# HandTracker.net
KiCad netlist of a schematic drawn in EAGLE
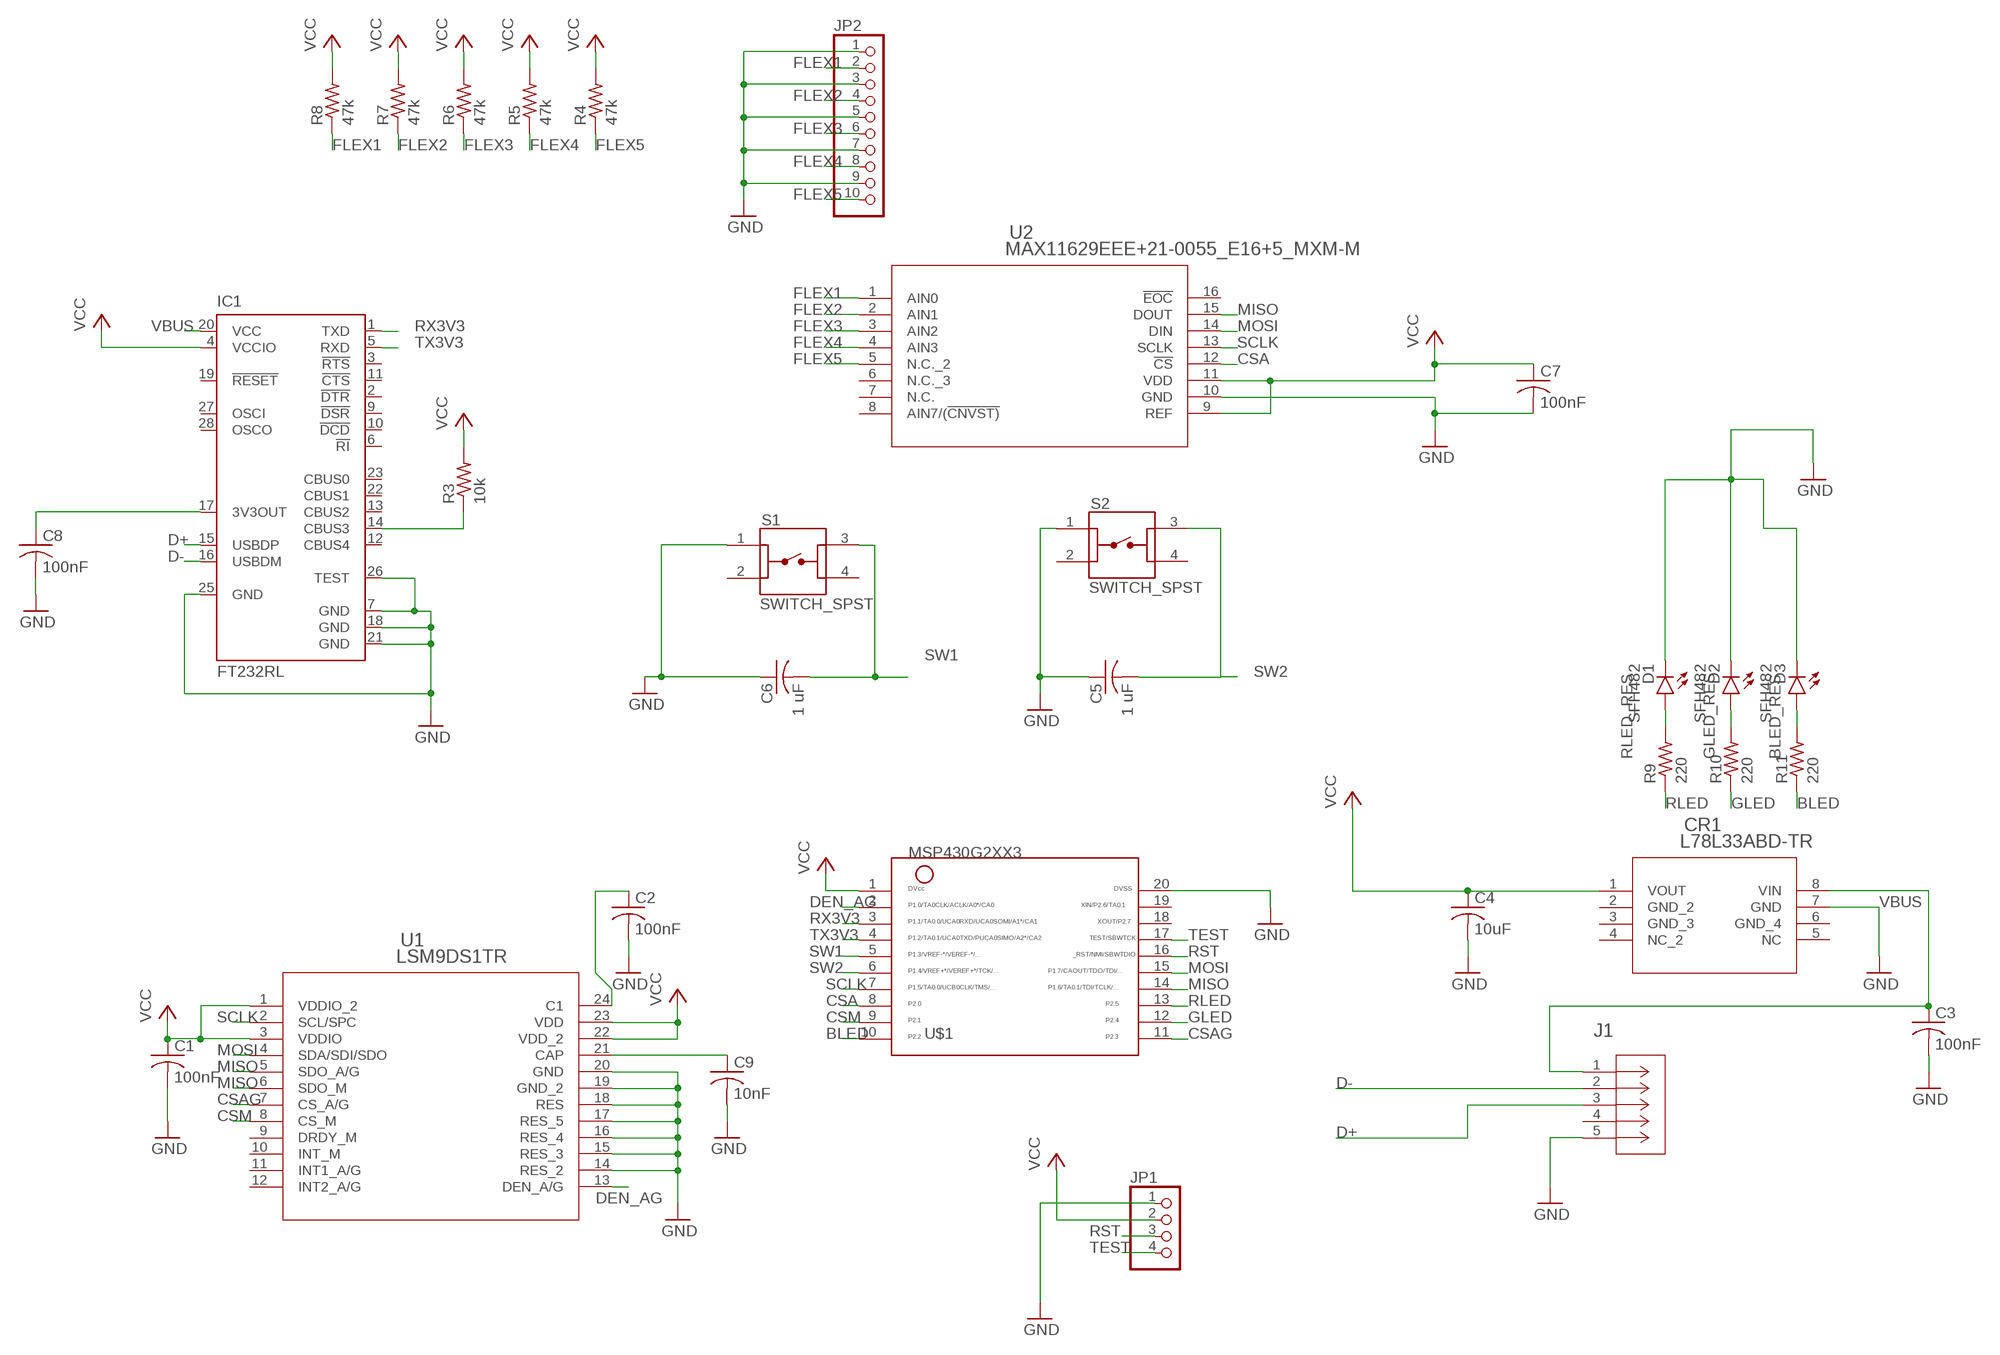
[diagram p0: schematic, sheet 1]

(export (version "E")
  (design (tool "Eeschema 10.0.6"))
  (components
    (comp (ref "C1")
      (value "100nF")
      (footprint "eagle-import:C1206")
      (libsource (lib "eagle-import") (part "C-USC1206"))
    )
    (comp (ref "C2")
      (value "100nF")
      (footprint "eagle-import:C1206")
      (libsource (lib "eagle-import") (part "C-USC1206"))
    )
    (comp (ref "C3")
      (value "100nF")
      (footprint "eagle-import:C1206")
      (libsource (lib "eagle-import") (part "C-USC1206"))
    )
    (comp (ref "C4")
      (value "10uF")
      (footprint "eagle-import:C1206")
      (libsource (lib "eagle-import") (part "C-USC1206"))
    )
    (comp (ref "C5")
      (value "1 uF")
      (footprint "eagle-import:C1206")
      (libsource (lib "eagle-import") (part "C-USC1206"))
    )
    (comp (ref "C6")
      (value "1 uF")
      (footprint "eagle-import:C1206")
      (libsource (lib "eagle-import") (part "C-USC1206"))
    )
    (comp (ref "C7")
      (value "100nF")
      (footprint "eagle-import:C1206")
      (libsource (lib "eagle-import") (part "C-USC1206"))
    )
    (comp (ref "C8")
      (value "100nF")
      (footprint "eagle-import:C1206")
      (libsource (lib "eagle-import") (part "C-USC1206"))
    )
    (comp (ref "C9")
      (value "10nF")
      (footprint "eagle-import:C1206")
      (libsource (lib "eagle-import") (part "C-USC1206"))
    )
    (comp (ref "CR1")
      (value "L78L33ABD-TR")
      (footprint "eagle-import:SO-8_STM")
      (fields (field (name "COPYRIGHT") "Copyright (C) 2022 Ultra Librarian. All rights reserved."))
      (libsource (lib "eagle-import") (part "L78L33ABD-TR"))
    )
    (comp (ref "D1")
      (value "SFH482")
      (footprint "eagle-import:SFH482")
      (libsource (lib "eagle-import") (part "SFH482"))
    )
    (comp (ref "D2")
      (value "SFH482")
      (footprint "eagle-import:SFH482")
      (libsource (lib "eagle-import") (part "SFH482"))
    )
    (comp (ref "D3")
      (value "SFH482")
      (footprint "eagle-import:SFH482")
      (libsource (lib "eagle-import") (part "SFH482"))
    )
    (comp (ref "IC1")
      (value "FT232RL")
      (footprint "eagle-import:SSOP28")
      (libsource (lib "eagle-import") (part "FT232RL"))
    )
    (comp (ref "J1")
      (value "ZX62-AB-5PA(31)")
      (footprint "eagle-import:CONN5_ZX62-AB-5PA_HIR")
      (fields (field (name "COPYRIGHT") "Copyright (C) 2022 Ultra Librarian. All rights reserved."))
      (libsource (lib "eagle-import") (part "ZX62-AB-5PA(31)"))
    )
    (comp (ref "JP1")
      (value "PINHD-1X4/90")
      (footprint "eagle-import:1X04_90")
      (libsource (lib "eagle-import") (part "PINHD-1X4/90"))
    )
    (comp (ref "JP2")
      (value "PINHD-1X10")
      (footprint "eagle-import:1X10")
      (libsource (lib "eagle-import") (part "PINHD-1X10"))
    )
    (comp (ref "R3")
      (value "10k")
      (footprint "eagle-import:R1206")
      (libsource (lib "eagle-import") (part "R-US_R1206"))
    )
    (comp (ref "R4")
      (value "47k")
      (footprint "eagle-import:R1206")
      (libsource (lib "eagle-import") (part "R-US_R1206"))
    )
    (comp (ref "R5")
      (value "47k")
      (footprint "eagle-import:R1206")
      (libsource (lib "eagle-import") (part "R-US_R1206"))
    )
    (comp (ref "R6")
      (value "47k")
      (footprint "eagle-import:R1206")
      (libsource (lib "eagle-import") (part "R-US_R1206"))
    )
    (comp (ref "R7")
      (value "47k")
      (footprint "eagle-import:R1206")
      (libsource (lib "eagle-import") (part "R-US_R1206"))
    )
    (comp (ref "R8")
      (value "47k")
      (footprint "eagle-import:R1206")
      (libsource (lib "eagle-import") (part "R-US_R1206"))
    )
    (comp (ref "R9")
      (value "220")
      (footprint "eagle-import:R1206")
      (libsource (lib "eagle-import") (part "R-US_R1206"))
    )
    (comp (ref "R10")
      (value "220")
      (footprint "eagle-import:R1206")
      (libsource (lib "eagle-import") (part "R-US_R1206"))
    )
    (comp (ref "R11")
      (value "220")
      (footprint "eagle-import:R1206")
      (libsource (lib "eagle-import") (part "R-US_R1206"))
    )
    (comp (ref "S1")
      (value "SWITCH_SPST")
      (footprint "eagle-import:SW_1825910-7")
      (fields
        (field (name "COMMENT") "1825910-7")
        (field (name "DIGI-KEY_PART_NUMBER") "450-1804-ND")
        (field (name "MF") "TE Connectivity")
      )
      (libsource (lib "eagle-import") (part "SWITCH_SPST"))
    )
    (comp (ref "S2")
      (value "SWITCH_SPST")
      (footprint "eagle-import:SW_1825910-7")
      (fields
        (field (name "COMMENT") "1825910-7")
        (field (name "DIGI-KEY_PART_NUMBER") "450-1804-ND")
        (field (name "MF") "TE Connectivity")
      )
      (libsource (lib "eagle-import") (part "SWITCH_SPST"))
    )
    (comp (ref "U$1")
      (value "MSP430G2XX3TSSOP")
      (footprint "eagle-import:PW20")
      (libsource (lib "eagle-import") (part "MSP430G2XX3TSSOP"))
    )
    (comp (ref "U1")
      (value "LSM9DS1TR")
      (footprint "eagle-import:LGA-24_3X3P5X1_STM")
      (fields (field (name "COPYRIGHT") "Copyright (C) 2022 Ultra Librarian. All rights reserved."))
      (libsource (lib "eagle-import") (part "LSM9DS1TR"))
    )
    (comp (ref "U2")
      (value "MAX11629EEE+21-0055_E16+5_MXM-M")
      (footprint "eagle-import:21-0055_E16+5_MXM-M")
      (fields
        (field (name "MANUFACTURER_PART_NUMBER") "MAX11629EEE+")
        (field (name "COPYRIGHT") "Copyright (C) 2022 Ultra Librarian. All rights reserved.")
      )
      (libsource (lib "eagle-import") (part "MAX11629EEE+21-0055_E16+5_MXM-M"))
    )
  )
  (nets
    (net (code "1") (name "/BLED") (class "Default")
      (node (ref "R11") (pin "1") (pinfunction "1_1") (pintype "passive"))
      (node (ref "U$1") (pin "10") (pinfunction "10_10") (pintype "bidirectional"))
    )
    (net (code "2") (name "/BLED_RES") (class "Default")
      (node (ref "D3") (pin "A") (pinfunction "A_A") (pintype "passive"))
      (node (ref "R11") (pin "2") (pinfunction "2_2") (pintype "passive"))
    )
    (net (code "3") (name "/CSA") (class "Default")
      (node (ref "U$1") (pin "8") (pinfunction "8_8") (pintype "bidirectional"))
      (node (ref "U2") (pin "12") (pinfunction "~{CS}_12") (pintype "bidirectional"))
    )
    (net (code "4") (name "/CSAG") (class "Default")
      (node (ref "U$1") (pin "11") (pinfunction "11_11") (pintype "bidirectional"))
      (node (ref "U1") (pin "7") (pinfunction "CS_A/G_7") (pintype "bidirectional"))
    )
    (net (code "5") (name "/CSM") (class "Default")
      (node (ref "U$1") (pin "9") (pinfunction "9_9") (pintype "bidirectional"))
      (node (ref "U1") (pin "8") (pinfunction "CS_M_8") (pintype "bidirectional"))
    )
    (net (code "6") (name "/D+") (class "Default")
      (node (ref "IC1") (pin "15") (pinfunction "USBDP_15") (pintype "bidirectional"))
      (node (ref "J1") (pin "3") (pinfunction "D+_3") (pintype "passive"))
    )
    (net (code "7") (name "/D-") (class "Default")
      (node (ref "IC1") (pin "16") (pinfunction "USBDM_16") (pintype "bidirectional"))
      (node (ref "J1") (pin "2") (pinfunction "D-_2") (pintype "passive"))
    )
    (net (code "8") (name "/DEN_AG") (class "Default")
      (node (ref "U$1") (pin "2") (pinfunction "2_2") (pintype "bidirectional"))
      (node (ref "U1") (pin "13") (pinfunction "DEN_A/G_13") (pintype "bidirectional"))
    )
    (net (code "9") (name "/FLEX1") (class "Default")
      (node (ref "JP2") (pin "2") (pinfunction "2_2") (pintype "passive"))
      (node (ref "R8") (pin "1") (pinfunction "1_1") (pintype "passive"))
      (node (ref "U2") (pin "1") (pinfunction "AIN0_1") (pintype "input"))
    )
    (net (code "10") (name "/FLEX2") (class "Default")
      (node (ref "JP2") (pin "4") (pinfunction "4_4") (pintype "passive"))
      (node (ref "R7") (pin "1") (pinfunction "1_1") (pintype "passive"))
      (node (ref "U2") (pin "2") (pinfunction "AIN1_2") (pintype "input"))
    )
    (net (code "11") (name "/FLEX3") (class "Default")
      (node (ref "JP2") (pin "6") (pinfunction "6_6") (pintype "passive"))
      (node (ref "R6") (pin "1") (pinfunction "1_1") (pintype "passive"))
      (node (ref "U2") (pin "3") (pinfunction "AIN2_3") (pintype "input"))
    )
    (net (code "12") (name "/FLEX4") (class "Default")
      (node (ref "JP2") (pin "8") (pinfunction "8_8") (pintype "passive"))
      (node (ref "R5") (pin "1") (pinfunction "1_1") (pintype "passive"))
      (node (ref "U2") (pin "4") (pinfunction "AIN3_4") (pintype "input"))
    )
    (net (code "13") (name "/FLEX5") (class "Default")
      (node (ref "JP2") (pin "10") (pinfunction "10_10") (pintype "passive"))
      (node (ref "R4") (pin "1") (pinfunction "1_1") (pintype "passive"))
      (node (ref "U2") (pin "5") (pinfunction "N.C._2_5") (pintype "bidirectional"))
    )
    (net (code "14") (name "/GLED") (class "Default")
      (node (ref "R10") (pin "1") (pinfunction "1_1") (pintype "passive"))
      (node (ref "U$1") (pin "12") (pinfunction "12_12") (pintype "bidirectional"))
    )
    (net (code "15") (name "/GLED_RES") (class "Default")
      (node (ref "D2") (pin "A") (pinfunction "A_A") (pintype "passive"))
      (node (ref "R10") (pin "2") (pinfunction "2_2") (pintype "passive"))
    )
    (net (code "16") (name "/MISO") (class "Default")
      (node (ref "U$1") (pin "14") (pinfunction "14_14") (pintype "bidirectional"))
      (node (ref "U1") (pin "5") (pinfunction "SDO_A/G_5") (pintype "output"))
      (node (ref "U1") (pin "6") (pinfunction "SDO_M_6") (pintype "output"))
      (node (ref "U2") (pin "15") (pinfunction "DOUT_15") (pintype "output"))
    )
    (net (code "17") (name "/MOSI") (class "Default")
      (node (ref "U$1") (pin "15") (pinfunction "15_15") (pintype "bidirectional"))
      (node (ref "U1") (pin "4") (pinfunction "SDA/SDI/SDO_4") (pintype "bidirectional"))
      (node (ref "U2") (pin "14") (pinfunction "DIN_14") (pintype "input"))
    )
    (net (code "18") (name "/RLED") (class "Default")
      (node (ref "R9") (pin "1") (pinfunction "1_1") (pintype "passive"))
      (node (ref "U$1") (pin "13") (pinfunction "13_13") (pintype "bidirectional"))
    )
    (net (code "19") (name "/RLED_RES") (class "Default")
      (node (ref "D1") (pin "A") (pinfunction "A_A") (pintype "passive"))
      (node (ref "R9") (pin "2") (pinfunction "2_2") (pintype "passive"))
    )
    (net (code "20") (name "/RST") (class "Default")
      (node (ref "JP1") (pin "3") (pinfunction "3_3") (pintype "passive"))
      (node (ref "U$1") (pin "16") (pinfunction "16_16") (pintype "bidirectional"))
    )
    (net (code "21") (name "/RX3V3") (class "Default")
      (node (ref "IC1") (pin "1") (pinfunction "TXD_1") (pintype "output"))
      (node (ref "U$1") (pin "3") (pinfunction "3_3") (pintype "bidirectional"))
    )
    (net (code "22") (name "/SCLK") (class "Default")
      (node (ref "U$1") (pin "7") (pinfunction "7_7") (pintype "bidirectional"))
      (node (ref "U1") (pin "2") (pinfunction "SCL/SPC_2") (pintype "bidirectional"))
      (node (ref "U2") (pin "13") (pinfunction "SCLK_13") (pintype "bidirectional"))
    )
    (net (code "23") (name "/SW1") (class "Default")
      (node (ref "C6") (pin "2") (pinfunction "2_2") (pintype "passive"))
      (node (ref "S1") (pin "3") (pinfunction "3_3") (pintype "passive"))
      (node (ref "U$1") (pin "5") (pinfunction "5_5") (pintype "bidirectional"))
    )
    (net (code "24") (name "/SW2") (class "Default")
      (node (ref "C5") (pin "2") (pinfunction "2_2") (pintype "passive"))
      (node (ref "S2") (pin "3") (pinfunction "3_3") (pintype "passive"))
      (node (ref "U$1") (pin "6") (pinfunction "6_6") (pintype "bidirectional"))
    )
    (net (code "25") (name "/TEST") (class "Default")
      (node (ref "JP1") (pin "4") (pinfunction "4_4") (pintype "passive"))
      (node (ref "U$1") (pin "17") (pinfunction "17_17") (pintype "bidirectional"))
    )
    (net (code "26") (name "/TX3V3") (class "Default")
      (node (ref "IC1") (pin "5") (pinfunction "RXD_5") (pintype "input"))
      (node (ref "U$1") (pin "4") (pinfunction "4_4") (pintype "bidirectional"))
    )
    (net (code "27") (name "/VBUS") (class "Default")
      (node (ref "C3") (pin "1") (pinfunction "1_1") (pintype "passive"))
      (node (ref "CR1") (pin "8") (pinfunction "VIN_8") (pintype "input"))
      (node (ref "IC1") (pin "20") (pinfunction "VCC_20") (pintype "power_in"))
      (node (ref "J1") (pin "1") (pinfunction "VCC_1") (pintype "passive"))
    )
    (net (code "28") (name "GND") (class "Default")
      (node (ref "C1") (pin "2") (pinfunction "2_2") (pintype "passive"))
      (node (ref "C2") (pin "2") (pinfunction "2_2") (pintype "passive"))
      (node (ref "C3") (pin "2") (pinfunction "2_2") (pintype "passive"))
      (node (ref "C4") (pin "2") (pinfunction "2_2") (pintype "passive"))
      (node (ref "C5") (pin "1") (pinfunction "1_1") (pintype "passive"))
      (node (ref "C6") (pin "1") (pinfunction "1_1") (pintype "passive"))
      (node (ref "C7") (pin "2") (pinfunction "2_2") (pintype "passive"))
      (node (ref "C8") (pin "2") (pinfunction "2_2") (pintype "passive"))
      (node (ref "C9") (pin "2") (pinfunction "2_2") (pintype "passive"))
      (node (ref "CR1") (pin "7") (pinfunction "GND_7") (pintype "passive"))
      (node (ref "D1") (pin "K") (pinfunction "C_K") (pintype "passive"))
      (node (ref "D2") (pin "K") (pinfunction "C_K") (pintype "passive"))
      (node (ref "D3") (pin "K") (pinfunction "C_K") (pintype "passive"))
      (node (ref "IC1") (pin "18") (pinfunction "GND_18") (pintype "power_in"))
      (node (ref "IC1") (pin "21") (pinfunction "GND_21") (pintype "power_in"))
      (node (ref "IC1") (pin "25") (pinfunction "GND_25") (pintype "power_in"))
      (node (ref "IC1") (pin "26") (pinfunction "TEST_26") (pintype "input"))
      (node (ref "IC1") (pin "7") (pinfunction "GND_7") (pintype "power_in"))
      (node (ref "J1") (pin "5") (pinfunction "GND_5") (pintype "passive"))
      (node (ref "JP1") (pin "1") (pinfunction "1_1") (pintype "passive"))
      (node (ref "JP2") (pin "1") (pinfunction "1_1") (pintype "passive"))
      (node (ref "JP2") (pin "3") (pinfunction "3_3") (pintype "passive"))
      (node (ref "JP2") (pin "5") (pinfunction "5_5") (pintype "passive"))
      (node (ref "JP2") (pin "7") (pinfunction "7_7") (pintype "passive"))
      (node (ref "JP2") (pin "9") (pinfunction "9_9") (pintype "passive"))
      (node (ref "S1") (pin "1") (pinfunction "1_1") (pintype "passive"))
      (node (ref "S2") (pin "1") (pinfunction "1_1") (pintype "passive"))
      (node (ref "U$1") (pin "20") (pinfunction "20_20") (pintype "bidirectional"))
      (node (ref "U1") (pin "14") (pinfunction "RES_2_14") (pintype "passive"))
      (node (ref "U1") (pin "15") (pinfunction "RES_3_15") (pintype "passive"))
      (node (ref "U1") (pin "16") (pinfunction "RES_4_16") (pintype "passive"))
      (node (ref "U1") (pin "17") (pinfunction "RES_5_17") (pintype "passive"))
      (node (ref "U1") (pin "18") (pinfunction "RES_18") (pintype "passive"))
      (node (ref "U1") (pin "19") (pinfunction "GND_2_19") (pintype "power_in"))
      (node (ref "U1") (pin "20") (pinfunction "GND_20") (pintype "power_in"))
      (node (ref "U2") (pin "10") (pinfunction "GND_10") (pintype "power_in"))
    )
    (net (code "29") (name "Net-(IC1-3V3OUT)") (class "Default")
      (node (ref "C8") (pin "1") (pinfunction "1_1") (pintype "passive"))
      (node (ref "IC1") (pin "17") (pinfunction "3V3OUT_17") (pintype "output"))
    )
    (net (code "30") (name "Net-(IC1-CBUS3)") (class "Default")
      (node (ref "IC1") (pin "14") (pinfunction "CBUS3_14") (pintype "bidirectional"))
      (node (ref "R3") (pin "1") (pinfunction "1_1") (pintype "passive"))
    )
    (net (code "31") (name "Net-(U1-C1)") (class "Default")
      (node (ref "C2") (pin "1") (pinfunction "1_1") (pintype "passive"))
      (node (ref "U1") (pin "24") (pinfunction "C1_24") (pintype "bidirectional"))
    )
    (net (code "32") (name "Net-(U1-CAP)") (class "Default")
      (node (ref "C9") (pin "1") (pinfunction "1_1") (pintype "passive"))
      (node (ref "U1") (pin "21") (pinfunction "CAP_21") (pintype "passive"))
    )
    (net (code "33") (name "VCC") (class "Default")
      (node (ref "C1") (pin "1") (pinfunction "1_1") (pintype "passive"))
      (node (ref "C4") (pin "1") (pinfunction "1_1") (pintype "passive"))
      (node (ref "C7") (pin "1") (pinfunction "1_1") (pintype "passive"))
      (node (ref "CR1") (pin "1") (pinfunction "VOUT_1") (pintype "output"))
      (node (ref "IC1") (pin "4") (pinfunction "VCCIO_4") (pintype "power_in"))
      (node (ref "JP1") (pin "2") (pinfunction "2_2") (pintype "passive"))
      (node (ref "R3") (pin "2") (pinfunction "2_2") (pintype "passive"))
      (node (ref "R4") (pin "2") (pinfunction "2_2") (pintype "passive"))
      (node (ref "R5") (pin "2") (pinfunction "2_2") (pintype "passive"))
      (node (ref "R6") (pin "2") (pinfunction "2_2") (pintype "passive"))
      (node (ref "R7") (pin "2") (pinfunction "2_2") (pintype "passive"))
      (node (ref "R8") (pin "2") (pinfunction "2_2") (pintype "passive"))
      (node (ref "U$1") (pin "1") (pinfunction "1_1") (pintype "bidirectional"))
      (node (ref "U1") (pin "1") (pinfunction "VDDIO_2_1") (pintype "power_in"))
      (node (ref "U1") (pin "22") (pinfunction "VDD_2_22") (pintype "power_in"))
      (node (ref "U1") (pin "23") (pinfunction "VDD_23") (pintype "power_in"))
      (node (ref "U1") (pin "3") (pinfunction "VDDIO_3") (pintype "power_in"))
      (node (ref "U2") (pin "11") (pinfunction "VDD_11") (pintype "power_in"))
      (node (ref "U2") (pin "9") (pinfunction "REF_9") (pintype "bidirectional"))
    )
    (net (code "34") (name "unconnected-(CR1-GND_2-Pad2)") (class "Default")
      (node (ref "CR1") (pin "2") (pinfunction "GND_2_2") (pintype "passive"))
    )
    (net (code "35") (name "unconnected-(CR1-GND_3-Pad3)") (class "Default")
      (node (ref "CR1") (pin "3") (pinfunction "GND_3_3") (pintype "passive"))
    )
    (net (code "36") (name "unconnected-(CR1-GND_4-Pad6)") (class "Default")
      (node (ref "CR1") (pin "6") (pinfunction "GND_4_6") (pintype "passive"))
    )
    (net (code "37") (name "unconnected-(CR1-NC-Pad5)") (class "Default")
      (node (ref "CR1") (pin "5") (pinfunction "NC_5") (pintype "no_connect"))
    )
    (net (code "38") (name "unconnected-(CR1-NC_2-Pad4)") (class "Default")
      (node (ref "CR1") (pin "4") (pinfunction "NC_2_4") (pintype "no_connect"))
    )
    (net (code "39") (name "unconnected-(IC1-CBUS0-Pad23)") (class "Default")
      (node (ref "IC1") (pin "23") (pinfunction "CBUS0_23") (pintype "bidirectional"))
    )
    (net (code "40") (name "unconnected-(IC1-CBUS1-Pad22)") (class "Default")
      (node (ref "IC1") (pin "22") (pinfunction "CBUS1_22") (pintype "bidirectional"))
    )
    (net (code "41") (name "unconnected-(IC1-CBUS2-Pad13)") (class "Default")
      (node (ref "IC1") (pin "13") (pinfunction "CBUS2_13") (pintype "bidirectional"))
    )
    (net (code "42") (name "unconnected-(IC1-CBUS4-Pad12)") (class "Default")
      (node (ref "IC1") (pin "12") (pinfunction "CBUS4_12") (pintype "bidirectional"))
    )
    (net (code "43") (name "unconnected-(IC1-OSCI-Pad27)") (class "Default")
      (node (ref "IC1") (pin "27") (pinfunction "OSCI_27") (pintype "input"))
    )
    (net (code "44") (name "unconnected-(IC1-OSCO-Pad28)") (class "Default")
      (node (ref "IC1") (pin "28") (pinfunction "OSCO_28") (pintype "output"))
    )
    (net (code "45") (name "unconnected-(IC1-~{CTS}-Pad11)") (class "Default")
      (node (ref "IC1") (pin "11") (pinfunction "~{CTS}_11") (pintype "input"))
    )
    (net (code "46") (name "unconnected-(IC1-~{DCD}-Pad10)") (class "Default")
      (node (ref "IC1") (pin "10") (pinfunction "~{DCD}_10") (pintype "input"))
    )
    (net (code "47") (name "unconnected-(IC1-~{DSR}-Pad9)") (class "Default")
      (node (ref "IC1") (pin "9") (pinfunction "~{DSR}_9") (pintype "input"))
    )
    (net (code "48") (name "unconnected-(IC1-~{DTR}-Pad2)") (class "Default")
      (node (ref "IC1") (pin "2") (pinfunction "~{DTR}_2") (pintype "output"))
    )
    (net (code "49") (name "unconnected-(IC1-~{RESET}-Pad19)") (class "Default")
      (node (ref "IC1") (pin "19") (pinfunction "~{RESET}_19") (pintype "input"))
    )
    (net (code "50") (name "unconnected-(IC1-~{RI}-Pad6)") (class "Default")
      (node (ref "IC1") (pin "6") (pinfunction "~{RI}_6") (pintype "input"))
    )
    (net (code "51") (name "unconnected-(IC1-~{RTS}-Pad3)") (class "Default")
      (node (ref "IC1") (pin "3") (pinfunction "~{RTS}_3") (pintype "output"))
    )
    (net (code "52") (name "unconnected-(J1-ID-Pad4)") (class "Default")
      (node (ref "J1") (pin "4") (pinfunction "ID_4") (pintype "passive"))
    )
    (net (code "53") (name "unconnected-(S1-Pad2)") (class "Default")
      (node (ref "S1") (pin "2") (pinfunction "2_2") (pintype "passive"))
    )
    (net (code "54") (name "unconnected-(S1-Pad4)") (class "Default")
      (node (ref "S1") (pin "4") (pinfunction "4_4") (pintype "passive"))
    )
    (net (code "55") (name "unconnected-(S2-Pad2)") (class "Default")
      (node (ref "S2") (pin "2") (pinfunction "2_2") (pintype "passive"))
    )
    (net (code "56") (name "unconnected-(S2-Pad4)") (class "Default")
      (node (ref "S2") (pin "4") (pinfunction "4_4") (pintype "passive"))
    )
    (net (code "57") (name "unconnected-(U$1-Pad18)") (class "Default")
      (node (ref "U$1") (pin "18") (pinfunction "18_18") (pintype "bidirectional"))
    )
    (net (code "58") (name "unconnected-(U$1-Pad19)") (class "Default")
      (node (ref "U$1") (pin "19") (pinfunction "19_19") (pintype "bidirectional"))
    )
    (net (code "59") (name "unconnected-(U1-DRDY_M-Pad9)") (class "Default")
      (node (ref "U1") (pin "9") (pinfunction "DRDY_M_9") (pintype "bidirectional"))
    )
    (net (code "60") (name "unconnected-(U1-INT1_A{slash}G-Pad11)") (class "Default")
      (node (ref "U1") (pin "11") (pinfunction "INT1_A/G_11") (pintype "bidirectional"))
    )
    (net (code "61") (name "unconnected-(U1-INT2_A{slash}G-Pad12)") (class "Default")
      (node (ref "U1") (pin "12") (pinfunction "INT2_A/G_12") (pintype "bidirectional"))
    )
    (net (code "62") (name "unconnected-(U1-INT_M-Pad10)") (class "Default")
      (node (ref "U1") (pin "10") (pinfunction "INT_M_10") (pintype "bidirectional"))
    )
    (net (code "63") (name "unconnected-(U2-AIN7{slash}(~{CNVST})-Pad8)") (class "Default")
      (node (ref "U2") (pin "8") (pinfunction "AIN7/(~{CNVST})_8") (pintype "bidirectional"))
    )
    (net (code "64") (name "unconnected-(U2-N.C.-Pad7)") (class "Default")
      (node (ref "U2") (pin "7") (pinfunction "N.C._7") (pintype "bidirectional"))
    )
    (net (code "65") (name "unconnected-(U2-N.C._3-Pad6)") (class "Default")
      (node (ref "U2") (pin "6") (pinfunction "N.C._3_6") (pintype "bidirectional"))
    )
    (net (code "66") (name "unconnected-(U2-~{EOC}-Pad16)") (class "Default")
      (node (ref "U2") (pin "16") (pinfunction "~{EOC}_16") (pintype "bidirectional"))
    )
  )
)
